# 32-009.net
KiCad netlist of a schematic drawn in Altium Designer
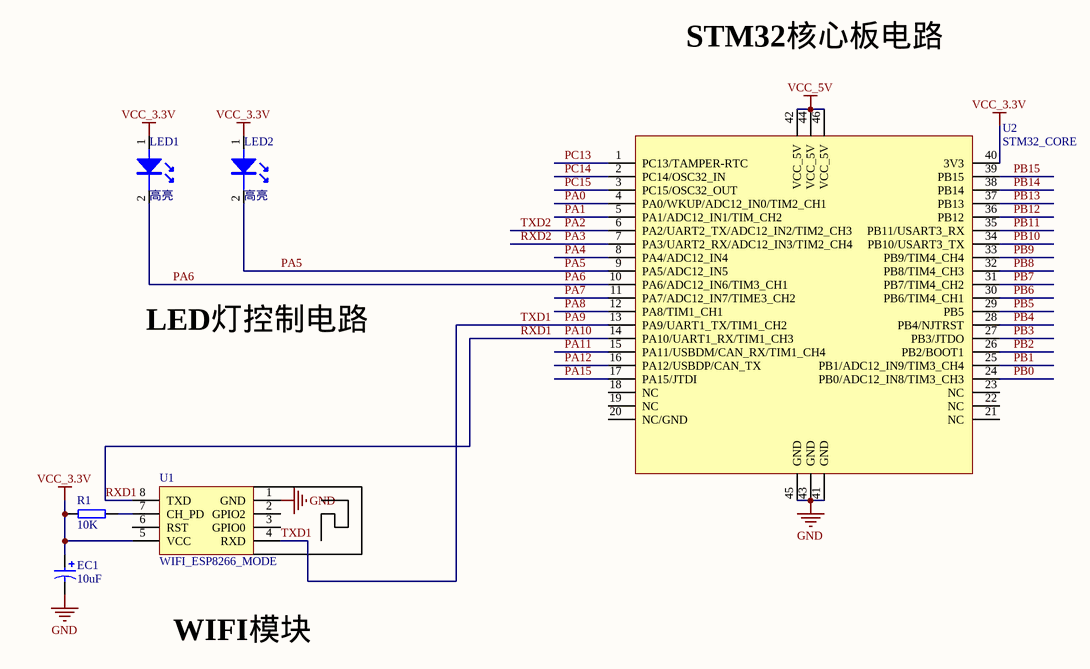
[diagram p0: 32-009原理图（源文件格式）.SchDoc]

(export (version "E")
  (design (tool "Eeschema 10.0.6"))
  (components
    (comp (ref "EC1")
      (value "10uF")
      (footprint "RB.1/.2")
      (description "极性电容")
      (libsource (lib "参考") (part "CAP_EC"))
    )
    (comp (ref "LED1")
      (value "高亮")
      (footprint "LED_D3MM12")
      (description "LED灯")
      (libsource (lib "参考") (part "LED"))
    )
    (comp (ref "LED2")
      (value "高亮")
      (footprint "LED_D3MM12")
      (description "LED灯")
      (libsource (lib "参考") (part "LED"))
    )
    (comp (ref "R1")
      (value "10K")
      (footprint "AXIAL0.3")
      (description "电阻")
      (libsource (lib "参考") (part "RES"))
    )
    (comp (ref "U1")
      (value "WIFI_ESP8266_MODE")
      (footprint "WIFI_ESP8266")
      (description "ESP8266/WIFI模块")
      (libsource (lib "参考") (part "WIFI_ESP8266_MODE"))
    )
    (comp (ref "U2")
      (value "STM32_CORE")
      (footprint "STM32_CORE")
      (description "STM32核心板")
      (libsource (lib "参考") (part "STM32_CORE"))
    )
  )
  (nets
    (net (code "1") (name "/PA0") (class "Default")
      (node (ref "U2") (pin "4") (pinfunction "PA0/WKUP/ADC12_IN0/TIM2_CH1_4") (pintype "passive"))
    )
    (net (code "2") (name "/PA1") (class "Default")
      (node (ref "U2") (pin "5") (pinfunction "PA1/ADC12_IN1/TIM_CH2_5") (pintype "passive"))
    )
    (net (code "3") (name "/PA2") (class "Default")
      (node (ref "U2") (pin "6") (pinfunction "PA2/UART2_TX/ADC12_IN2/TIM2_CH3_6") (pintype "passive"))
    )
    (net (code "4") (name "/PA3") (class "Default")
      (node (ref "U2") (pin "7") (pinfunction "PA3/UART2_RX/ADC12_IN3/TIM2_CH4_7") (pintype "passive"))
    )
    (net (code "5") (name "/PA4") (class "Default")
      (node (ref "U2") (pin "8") (pinfunction "PA4/ADC12_IN4_8") (pintype "passive"))
    )
    (net (code "6") (name "/PA5") (class "Default")
      (node (ref "LED2") (pin "2") (pinfunction "2_2") (pintype "passive"))
      (node (ref "U2") (pin "9") (pinfunction "PA5/ADC12_IN5_9") (pintype "passive"))
    )
    (net (code "7") (name "/PA6") (class "Default")
      (node (ref "LED1") (pin "2") (pinfunction "2_2") (pintype "passive"))
      (node (ref "U2") (pin "10") (pinfunction "PA6/ADC12_IN6/TIM3_CH1_10") (pintype "passive"))
    )
    (net (code "8") (name "/PA7") (class "Default")
      (node (ref "U2") (pin "11") (pinfunction "PA7/ADC12_IN7/TIME3_CH2_11") (pintype "passive"))
    )
    (net (code "9") (name "/PA8") (class "Default")
      (node (ref "U2") (pin "12") (pinfunction "PA8/TIM1_CH1_12") (pintype "passive"))
    )
    (net (code "10") (name "/PA9") (class "Default")
      (node (ref "U1") (pin "4") (pinfunction "RXD_4") (pintype "passive"))
      (node (ref "U2") (pin "13") (pinfunction "PA9/UART1_TX/TIM1_CH2_13") (pintype "passive"))
    )
    (net (code "11") (name "/PA10") (class "Default")
      (node (ref "U1") (pin "8") (pinfunction "TXD_8") (pintype "passive"))
      (node (ref "U2") (pin "14") (pinfunction "PA10/UART1_RX/TIM1_CH3_14") (pintype "passive"))
    )
    (net (code "12") (name "/PA11") (class "Default")
      (node (ref "U2") (pin "15") (pinfunction "PA11/USBDM/CAN_RX/TIM1_CH4_15") (pintype "passive"))
    )
    (net (code "13") (name "/PA12") (class "Default")
      (node (ref "U2") (pin "16") (pinfunction "PA12/USBDP/CAN_TX_16") (pintype "passive"))
    )
    (net (code "14") (name "/PA15") (class "Default")
      (node (ref "U2") (pin "17") (pinfunction "PA15/JTDI_17") (pintype "passive"))
    )
    (net (code "15") (name "/PB0") (class "Default")
      (node (ref "U2") (pin "24") (pinfunction "PB0/ADC12_IN8/TIM3_CH3_24") (pintype "passive"))
    )
    (net (code "16") (name "/PB1") (class "Default")
      (node (ref "U2") (pin "25") (pinfunction "PB1/ADC12_IN9/TIM3_CH4_25") (pintype "passive"))
    )
    (net (code "17") (name "/PB2") (class "Default")
      (node (ref "U2") (pin "26") (pinfunction "PB2/BOOT1_26") (pintype "passive"))
    )
    (net (code "18") (name "/PB3") (class "Default")
      (node (ref "U2") (pin "27") (pinfunction "PB3/JTDO_27") (pintype "passive"))
    )
    (net (code "19") (name "/PB4") (class "Default")
      (node (ref "U2") (pin "28") (pinfunction "PB4/NJTRST_28") (pintype "passive"))
    )
    (net (code "20") (name "/PB5") (class "Default")
      (node (ref "U2") (pin "29") (pinfunction "PB5_29") (pintype "passive"))
    )
    (net (code "21") (name "/PB6") (class "Default")
      (node (ref "U2") (pin "30") (pinfunction "PB6/TIM4_CH1_30") (pintype "passive"))
    )
    (net (code "22") (name "/PB7") (class "Default")
      (node (ref "U2") (pin "31") (pinfunction "PB7/TIM4_CH2_31") (pintype "passive"))
    )
    (net (code "23") (name "/PB8") (class "Default")
      (node (ref "U2") (pin "32") (pinfunction "PB8/TIM4_CH3_32") (pintype "passive"))
    )
    (net (code "24") (name "/PB9") (class "Default")
      (node (ref "U2") (pin "33") (pinfunction "PB9/TIM4_CH4_33") (pintype "passive"))
    )
    (net (code "25") (name "/PB10") (class "Default")
      (node (ref "U2") (pin "34") (pinfunction "PB10/USART3_TX_34") (pintype "passive"))
    )
    (net (code "26") (name "/PB11") (class "Default")
      (node (ref "U2") (pin "35") (pinfunction "PB11/USART3_RX_35") (pintype "passive"))
    )
    (net (code "27") (name "/PB12") (class "Default")
      (node (ref "U2") (pin "36") (pinfunction "PB12_36") (pintype "passive"))
    )
    (net (code "28") (name "/PB13") (class "Default")
      (node (ref "U2") (pin "37") (pinfunction "PB13_37") (pintype "passive"))
    )
    (net (code "29") (name "/PB14") (class "Default")
      (node (ref "U2") (pin "38") (pinfunction "PB14_38") (pintype "passive"))
    )
    (net (code "30") (name "/PB15") (class "Default")
      (node (ref "U2") (pin "39") (pinfunction "PB15_39") (pintype "passive"))
    )
    (net (code "31") (name "/PC13") (class "Default")
      (node (ref "U2") (pin "1") (pinfunction "PC13/TAMPER-RTC_1") (pintype "passive"))
    )
    (net (code "32") (name "/PC14") (class "Default")
      (node (ref "U2") (pin "2") (pinfunction "PC14/OSC32_IN_2") (pintype "passive"))
    )
    (net (code "33") (name "/PC15") (class "Default")
      (node (ref "U2") (pin "3") (pinfunction "PC15/OSC32_OUT_3") (pintype "passive"))
    )
    (net (code "34") (name "GND") (class "Default")
      (node (ref "EC1") (pin "2") (pinfunction "2_2") (pintype "passive"))
      (node (ref "U1") (pin "1") (pinfunction "GND_1") (pintype "passive"))
      (node (ref "U2") (pin "41") (pinfunction "GND_41") (pintype "passive"))
      (node (ref "U2") (pin "43") (pinfunction "GND_43") (pintype "passive"))
      (node (ref "U2") (pin "45") (pinfunction "GND_45") (pintype "passive"))
    )
    (net (code "35") (name "Net-(U1-CH_PD)") (class "Default")
      (node (ref "R1") (pin "1") (pinfunction "1_1") (pintype "passive"))
      (node (ref "U1") (pin "7") (pinfunction "CH_PD_7") (pintype "passive"))
    )
    (net (code "36") (name "VCC_3.3V") (class "Default")
      (node (ref "EC1") (pin "1") (pinfunction "1_1") (pintype "passive"))
      (node (ref "LED1") (pin "1") (pinfunction "1_1") (pintype "passive"))
      (node (ref "LED2") (pin "1") (pinfunction "1_1") (pintype "passive"))
      (node (ref "R1") (pin "2") (pinfunction "2_2") (pintype "passive"))
      (node (ref "U1") (pin "5") (pinfunction "VCC_5") (pintype "passive"))
      (node (ref "U2") (pin "40") (pinfunction "3V3_40") (pintype "passive"))
    )
    (net (code "37") (name "VCC_5V") (class "Default")
      (node (ref "U2") (pin "42") (pinfunction "VCC_5V_42") (pintype "passive"))
      (node (ref "U2") (pin "44") (pinfunction "VCC_5V_44") (pintype "passive"))
      (node (ref "U2") (pin "46") (pinfunction "VCC_5V_46") (pintype "passive"))
    )
    (net (code "38") (name "unconnected-(U1-GPIO0-Pad3)") (class "Default")
      (node (ref "U1") (pin "3") (pinfunction "GPIO0_3") (pintype "passive"))
    )
    (net (code "39") (name "unconnected-(U1-GPIO2-Pad2)") (class "Default")
      (node (ref "U1") (pin "2") (pinfunction "GPIO2_2") (pintype "passive"))
    )
    (net (code "40") (name "unconnected-(U1-RST-Pad6)") (class "Default")
      (node (ref "U1") (pin "6") (pinfunction "RST_6") (pintype "passive"))
    )
    (net (code "41") (name "unconnected-(U2-NC-Pad18)") (class "Default")
      (node (ref "U2") (pin "18") (pinfunction "NC_18") (pintype "passive"))
    )
    (net (code "42") (name "unconnected-(U2-NC-Pad19)") (class "Default")
      (node (ref "U2") (pin "19") (pinfunction "NC_19") (pintype "passive"))
    )
    (net (code "43") (name "unconnected-(U2-NC-Pad21)") (class "Default")
      (node (ref "U2") (pin "21") (pinfunction "NC_21") (pintype "passive"))
    )
    (net (code "44") (name "unconnected-(U2-NC-Pad22)") (class "Default")
      (node (ref "U2") (pin "22") (pinfunction "NC_22") (pintype "passive"))
    )
    (net (code "45") (name "unconnected-(U2-NC-Pad23)") (class "Default")
      (node (ref "U2") (pin "23") (pinfunction "NC_23") (pintype "passive"))
    )
    (net (code "46") (name "unconnected-(U2-NC{slash}GND-Pad20)") (class "Default")
      (node (ref "U2") (pin "20") (pinfunction "NC/GND_20") (pintype "passive"))
    )
  )
)
